# pcb_bare_tmc_2209.net
KiCad netlist of a schematic drawn in EAGLE
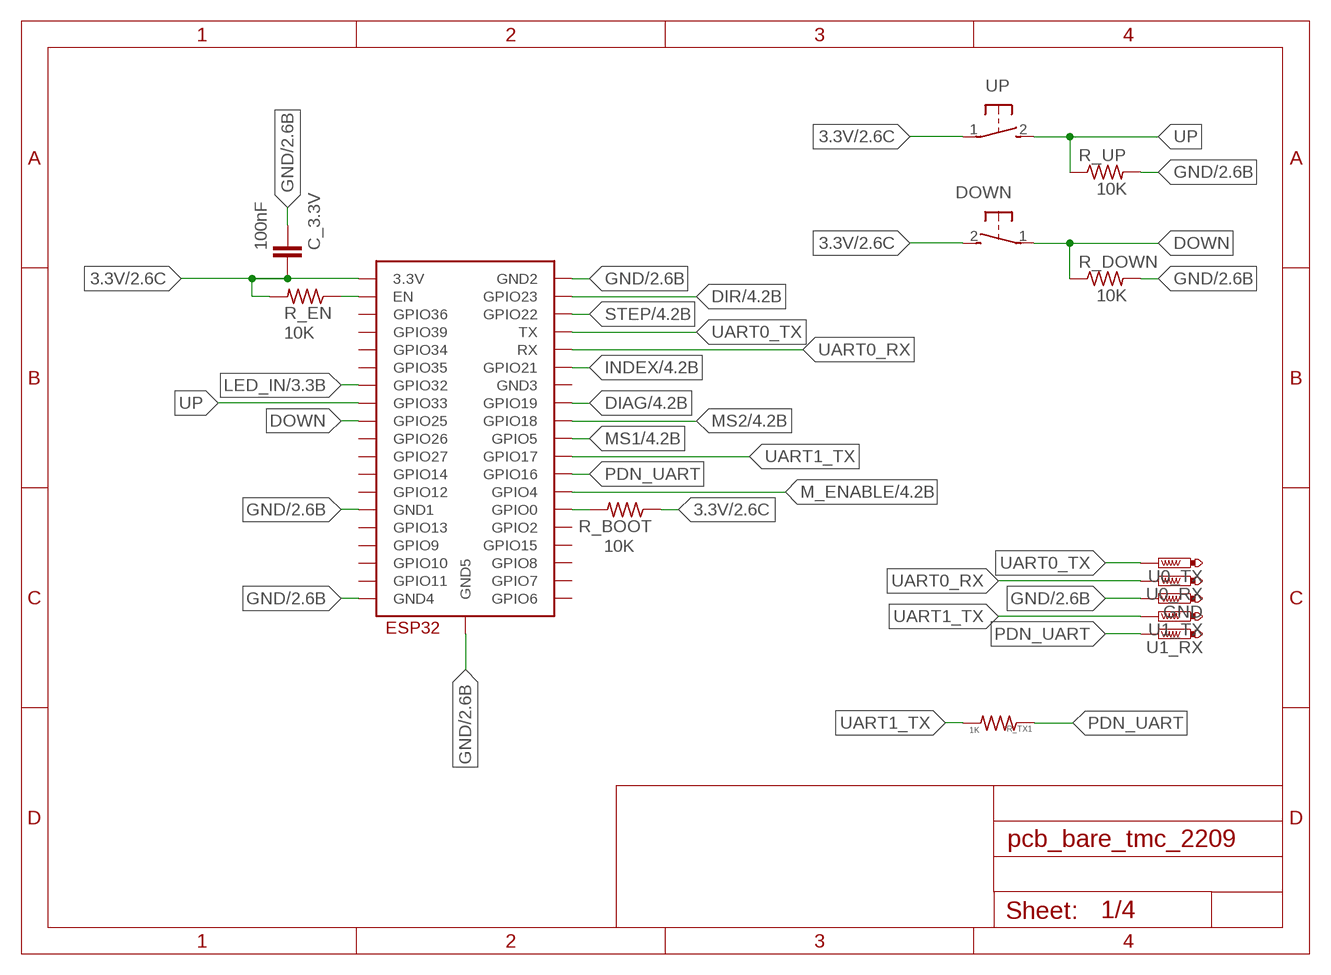
[diagram p0: schematic, sheet 1]
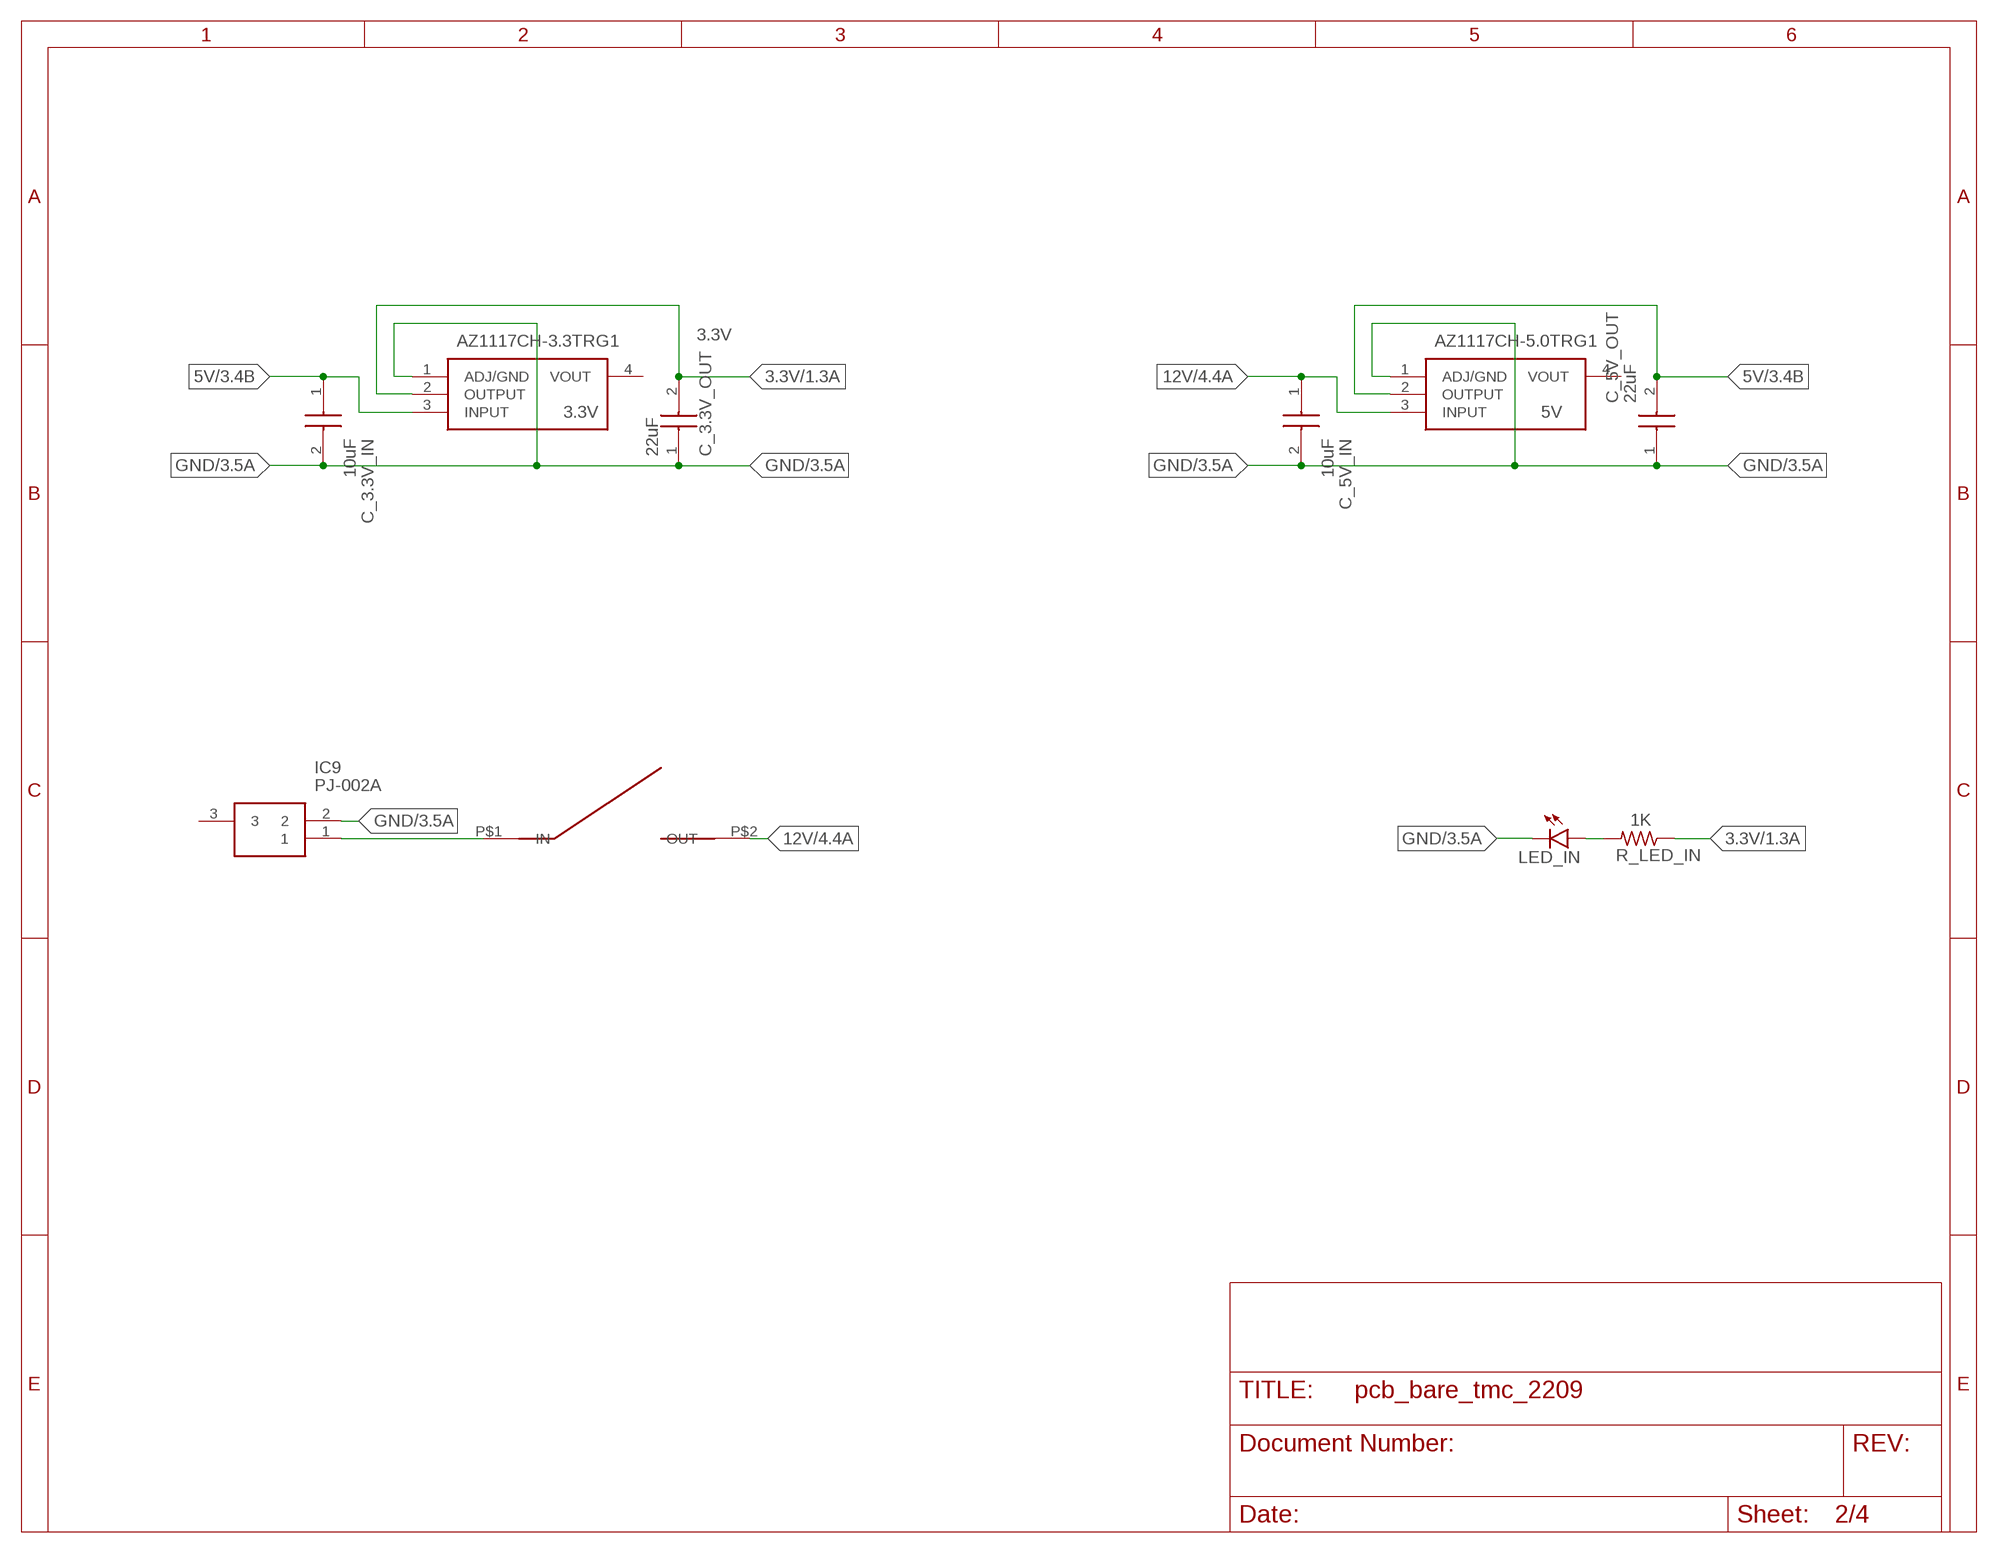
[diagram p1: schematic, sheet 2]
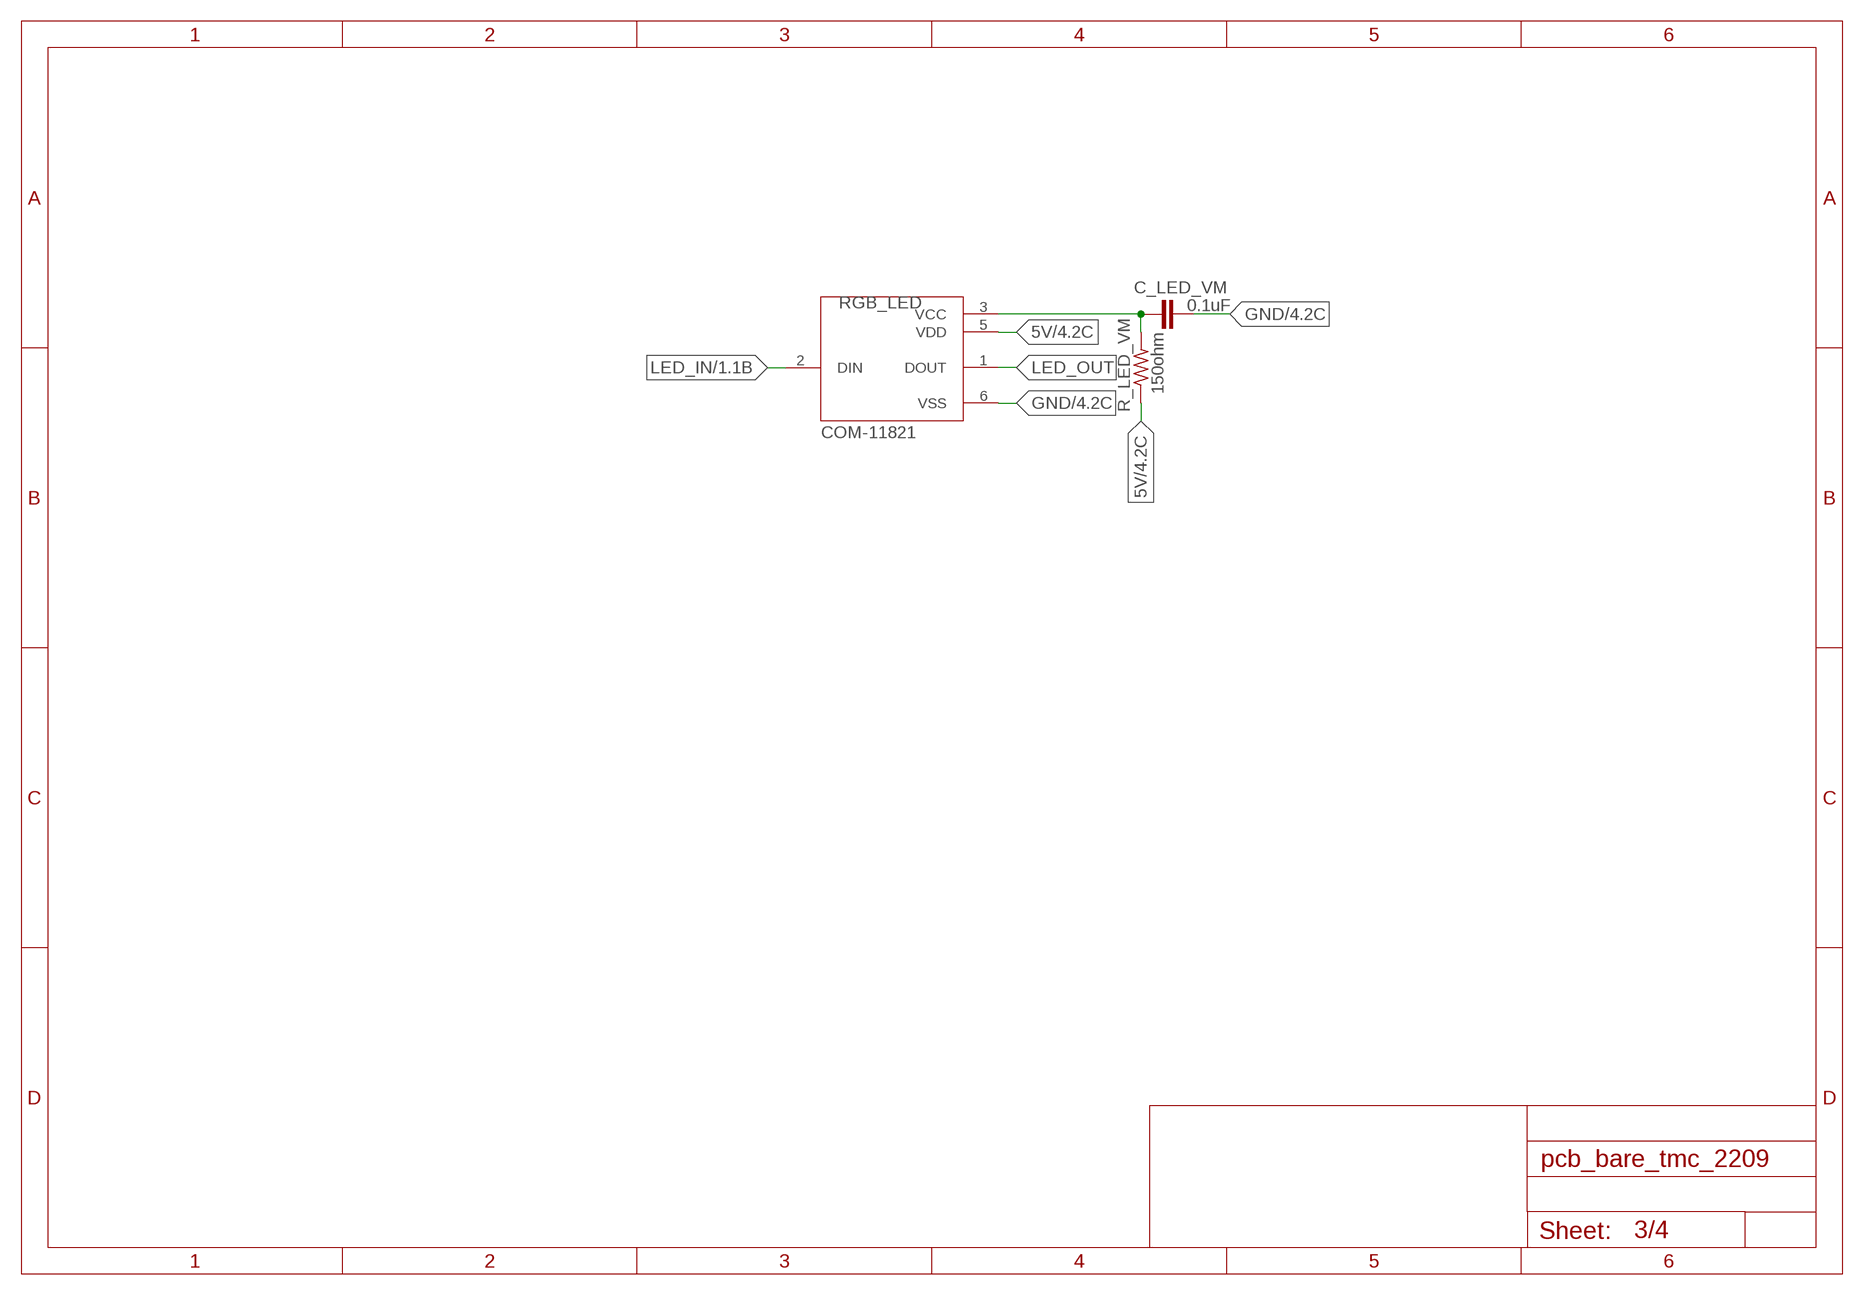
[diagram p2: schematic, sheet 3]
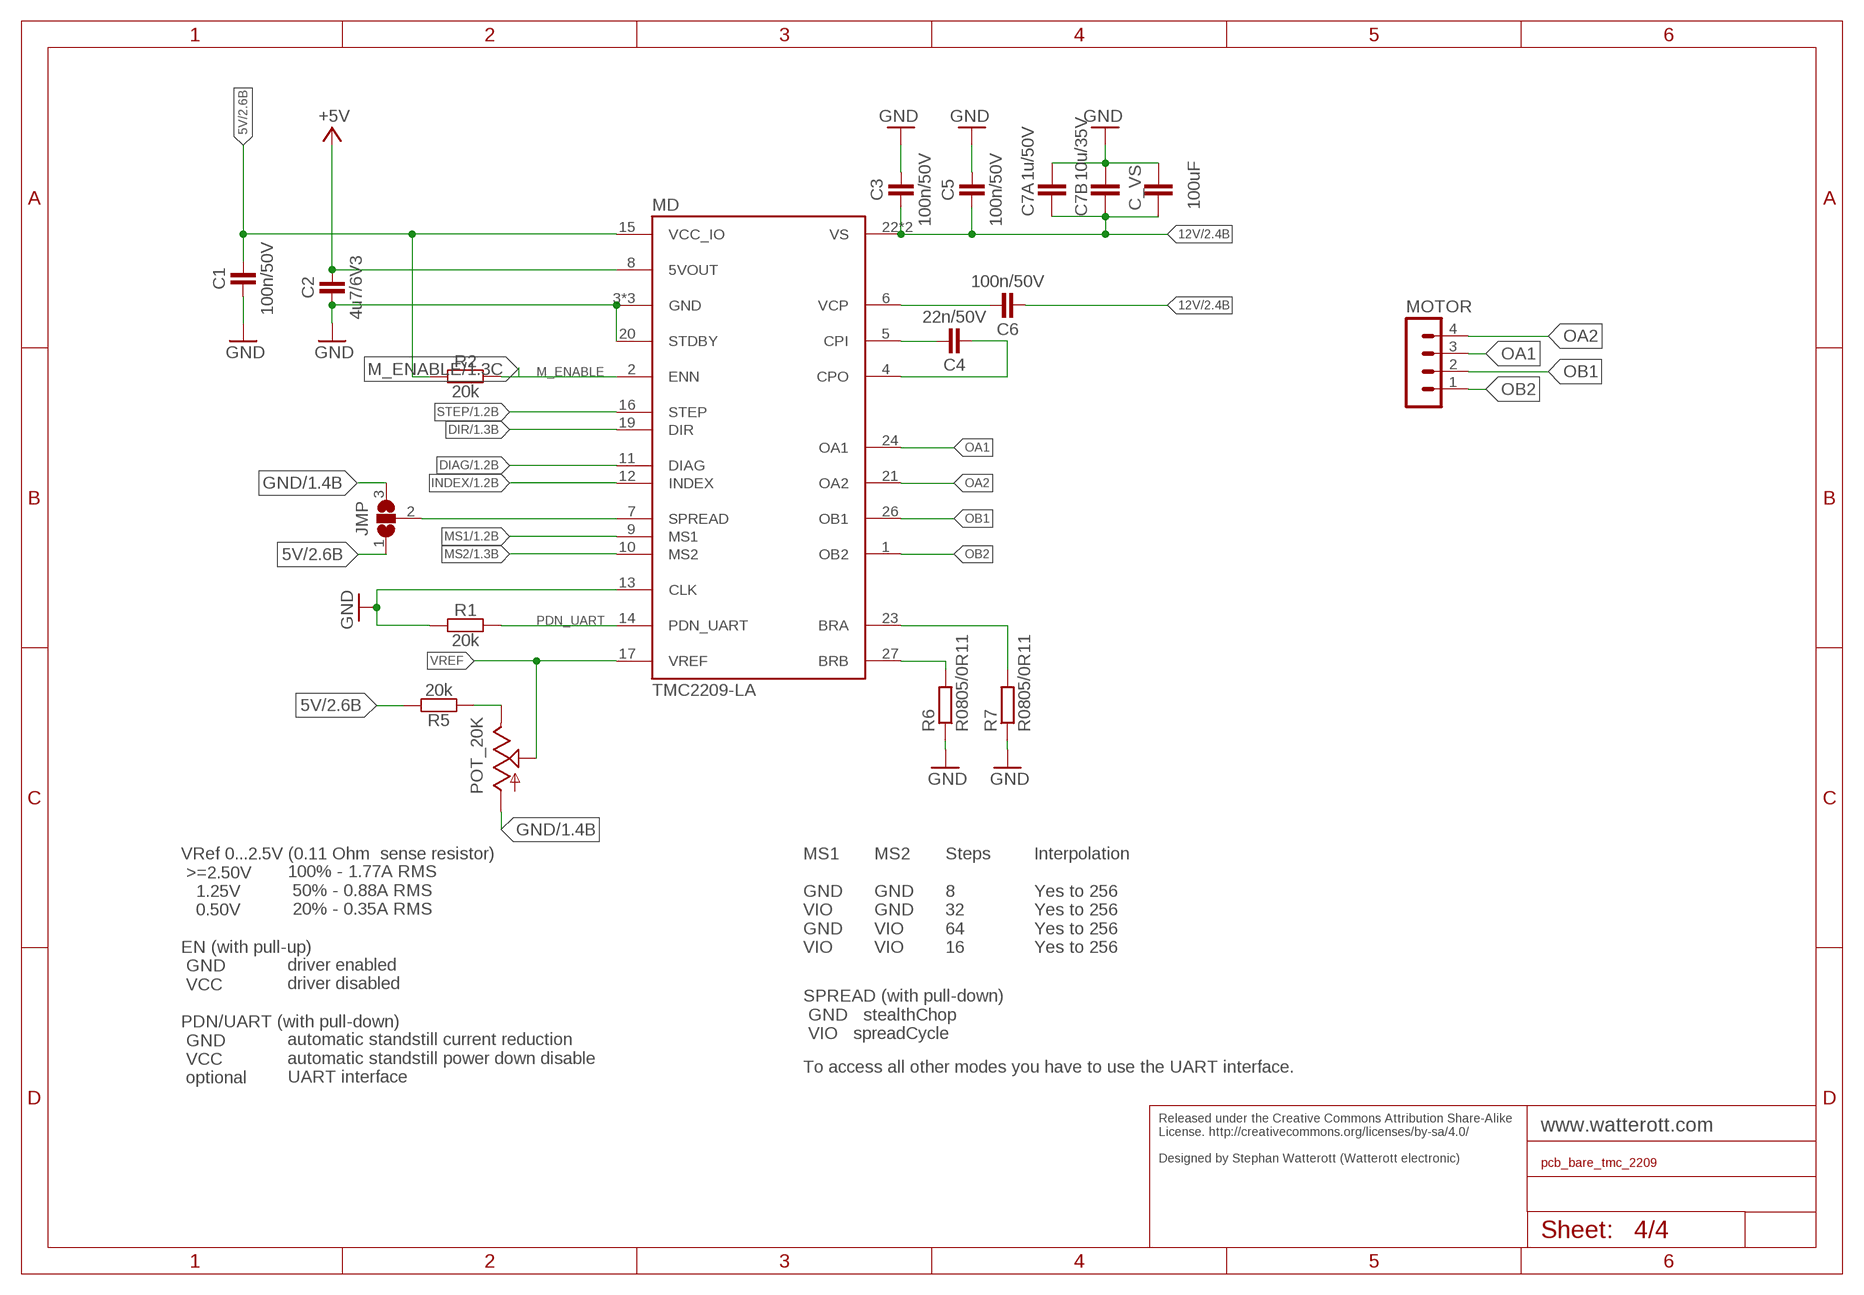
[diagram p3: schematic, sheet 4]

(export (version "E")
  (design (tool "Eeschema 10.0.6"))
  (components
    (comp (ref "C_LED_VM")
      (value "0.1uF")
      (footprint "eagle-import:C0805K")
      (libsource (lib "eagle-import") (part "rcl_334_C-EUC0805K"))
    )
    (comp (ref "RGB_LED")
      (value "COM-11821")
      (footprint "eagle-import:LED_COM-11821")
      (fields (field (name "MF") "SparkFun Electronics"))
      (libsource (lib "eagle-import") (part "COM-11821"))
    )
    (comp (ref "R_LED_VM")
      (value "150ohm")
      (footprint "eagle-import:R0805")
      (libsource (lib "eagle-import") (part "R-US_R0805"))
    )
    (comp (ref "C_3.3V")
      (value "100nF")
      (footprint "eagle-import:C0805K")
      (libsource (lib "eagle-import") (part "rcl_334_C-EUC0805K"))
    )
    (comp (ref "DOWN")
      (value "31-XX")
      (footprint "eagle-import:B3F-31XX")
      (fields (field (name "MPN") "B3F-3100"))
      (libsource (lib "eagle-import") (part "31-XX"))
    )
    (comp (ref "GND")
      (value "PTR1TP20SQ")
      (footprint "eagle-import:TP20SQ")
      (libsource (lib "eagle-import") (part "PTR1TP20SQ"))
    )
    (comp (ref "R_BOOT")
      (value "10K")
      (footprint "eagle-import:R0805")
      (libsource (lib "eagle-import") (part "R-US_R0805"))
    )
    (comp (ref "R_DOWN")
      (value "10K")
      (footprint "eagle-import:R0805")
      (libsource (lib "eagle-import") (part "R-US_R0805"))
    )
    (comp (ref "R_EN")
      (value "10K")
      (footprint "eagle-import:R0805")
      (libsource (lib "eagle-import") (part "R-US_R0805"))
    )
    (comp (ref "R_TX1")
      (value "1K")
      (footprint "eagle-import:R0805")
      (libsource (lib "eagle-import") (part "R-US_R0805"))
    )
    (comp (ref "R_UP")
      (value "10K")
      (footprint "eagle-import:R0805")
      (libsource (lib "eagle-import") (part "R-US_R0805"))
    )
    (comp (ref "U$2")
      (value "ESP32-WROOM")
      (footprint "eagle-import:ESP32-WROOM")
      (libsource (lib "eagle-import") (part "ESP32-WROOM"))
    )
    (comp (ref "U0_RX")
      (value "PTR1TP20SQ")
      (footprint "eagle-import:TP20SQ")
      (libsource (lib "eagle-import") (part "PTR1TP20SQ"))
    )
    (comp (ref "U0_TX")
      (value "PTR1TP20SQ")
      (footprint "eagle-import:TP20SQ")
      (libsource (lib "eagle-import") (part "PTR1TP20SQ"))
    )
    (comp (ref "U1_RX")
      (value "PTR1TP20SQ")
      (footprint "eagle-import:TP20SQ")
      (libsource (lib "eagle-import") (part "PTR1TP20SQ"))
    )
    (comp (ref "U1_TX")
      (value "PTR1TP20SQ")
      (footprint "eagle-import:TP20SQ")
      (libsource (lib "eagle-import") (part "PTR1TP20SQ"))
    )
    (comp (ref "UP")
      (value "31-XX")
      (footprint "eagle-import:B3F-31XX")
      (fields (field (name "MPN") "B3F-3100"))
      (libsource (lib "eagle-import") (part "31-XX"))
    )
    (comp (ref "3.3V")
      (value "AZ1117CH-3.3TRG1")
      (footprint "eagle-import:SOT230P700X180-4N")
      (fields (field (name "MOUSER_PART_NUMBER") "621-AZ1117CH-3.3TRG1"))
      (libsource (lib "eagle-import") (part "AZ1117CH-3.3TRG1"))
    )
    (comp (ref "5V")
      (value "AZ1117CH-5.0TRG1")
      (footprint "eagle-import:SOT230P700X180-4N")
      (fields (field (name "MOUSER_PART_NUMBER") "621-AZ1117CH-5.0TRG1"))
      (libsource (lib "eagle-import") (part "AZ1117CH-5.0TRG1"))
    )
    (comp (ref "C_3.3V_IN")
      (value "10uF")
      (footprint "eagle-import:CAPC2013X95N")
      (fields
        (field (name "MANUFACTURER_PART_NUMBER") "EMK212ABJ106KD-T")
        (field (name "MOUSER_PART_NUMBER") "963-EMK212ABJ106KD-T")
      )
      (libsource (lib "eagle-import") (part "EMK212ABJ106KD-T"))
    )
    (comp (ref "C_3.3V_OUT")
      (value "22uF")
      (footprint "eagle-import:CAPC3216X100N")
      (fields
        (field (name "MANUFACTURER_PART_NUMBER") "CL31A226MOCLNNC")
        (field (name "MOUSER_PART_NUMBER") "187-CL31A226MOCLNNC")
      )
      (libsource (lib "eagle-import") (part "CL31A226MOCLNNC"))
    )
    (comp (ref "C_5V_IN")
      (value "10uF")
      (footprint "eagle-import:CAPC2013X95N")
      (fields
        (field (name "MANUFACTURER_PART_NUMBER") "EMK212ABJ106KD-T")
        (field (name "MOUSER_PART_NUMBER") "963-EMK212ABJ106KD-T")
      )
      (libsource (lib "eagle-import") (part "EMK212ABJ106KD-T"))
    )
    (comp (ref "C_5V_OUT")
      (value "22uF")
      (footprint "eagle-import:CAPC3216X100N")
      (fields
        (field (name "MANUFACTURER_PART_NUMBER") "CL31A226MOCLNNC")
        (field (name "MOUSER_PART_NUMBER") "187-CL31A226MOCLNNC")
      )
      (libsource (lib "eagle-import") (part "CL31A226MOCLNNC"))
    )
    (comp (ref "IC9")
      (value "PJ-002A")
      (footprint "eagle-import:PJ002A")
      (fields (field (name "MOUSER_PART_NUMBER") "490-PJ-002A"))
      (libsource (lib "eagle-import") (part "PJ-002A"))
    )
    (comp (ref "LED_IN")
      (value "LEDSML0805")
      (footprint "eagle-import:SML0805")
      (libsource (lib "eagle-import") (part "LEDSML0805"))
    )
    (comp (ref "R_LED_IN")
      (value "1K")
      (footprint "eagle-import:R0805")
      (libsource (lib "eagle-import") (part "R-US_R0805"))
    )
    (comp (ref "U$1")
      (value "SPSTROCKERSWITCH2PIN")
      (footprint "eagle-import:SPST2PINROCKER")
      (libsource (lib "eagle-import") (part "SPSTROCKERSWITCH2PIN"))
    )
    (comp (ref "C1")
      (value "100n/50V")
      (footprint "eagle-import:C0402")
      (libsource (lib "eagle-import") (part "CAPACITOR-0402"))
    )
    (comp (ref "C2")
      (value "4u7/6V3")
      (footprint "eagle-import:C0402")
      (libsource (lib "eagle-import") (part "CAPACITOR-0402"))
    )
    (comp (ref "C3")
      (value "100n/50V")
      (footprint "eagle-import:C0402")
      (libsource (lib "eagle-import") (part "CAPACITOR-0402"))
    )
    (comp (ref "C4")
      (value "22n/50V")
      (footprint "eagle-import:C0402")
      (libsource (lib "eagle-import") (part "CAPACITOR-0402"))
    )
    (comp (ref "C5")
      (value "100n/50V")
      (footprint "eagle-import:C0402")
      (libsource (lib "eagle-import") (part "CAPACITOR-0402"))
    )
    (comp (ref "C6")
      (value "100n/50V")
      (footprint "eagle-import:C0402")
      (libsource (lib "eagle-import") (part "CAPACITOR-0402"))
    )
    (comp (ref "C7A")
      (value "1u/50V")
      (footprint "eagle-import:C0805")
      (libsource (lib "eagle-import") (part "C-EUC0805"))
    )
    (comp (ref "C7B")
      (value "10u/35V")
      (footprint "eagle-import:C1206")
      (libsource (lib "eagle-import") (part "C-EUC1206"))
    )
    (comp (ref "C_VS")
      (value "100uF")
      (footprint "eagle-import:C2.5-3")
      (libsource (lib "eagle-import") (part "C2,5-3"))
    )
    (comp (ref "JMP")
      (value "JUMPER3-0402-NC")
      (footprint "eagle-import:JUMPER3-0402_NC")
      (libsource (lib "eagle-import") (part "JUMPER3-0402-NC"))
    )
    (comp (ref "MD")
      (value "TMC2209-LA")
      (footprint "eagle-import:QFN28-PAD3.7")
      (libsource (lib "eagle-import") (part "TMC2209-LA"))
    )
    (comp (ref "MOTOR")
      (value "MA04-1")
      (footprint "eagle-import:MA04-1")
      (libsource (lib "eagle-import") (part "MA04-1"))
    )
    (comp (ref "POT_20K")
      (value "TRIM_US-3223G")
      (footprint "eagle-import:3223G")
      (libsource (lib "eagle-import") (part "TRIM_US-3223G"))
    )
    (comp (ref "R1")
      (value "20k")
      (footprint "eagle-import:C0402")
      (libsource (lib "eagle-import") (part "RESISTOR-0402"))
    )
    (comp (ref "R2")
      (value "20k")
      (footprint "eagle-import:C0402")
      (libsource (lib "eagle-import") (part "RESISTOR-0402"))
    )
    (comp (ref "R5")
      (value "20k")
      (footprint "eagle-import:C0402")
      (libsource (lib "eagle-import") (part "RESISTOR-0402"))
    )
    (comp (ref "R6")
      (value "R0805/0R11")
      (footprint "eagle-import:M0805")
      (libsource (lib "eagle-import") (part "R-EU_M0805"))
    )
    (comp (ref "R7")
      (value "R0805/0R11")
      (footprint "eagle-import:M0805")
      (libsource (lib "eagle-import") (part "R-EU_M0805"))
    )
  )
  (nets
    (net (code "1") (name "+5V") (class "Default")
      (node (ref "C2") (pin "2") (pinfunction "2_2") (pintype "passive"))
      (node (ref "MD") (pin "8") (pinfunction "5VOUT_8") (pintype "power_in"))
    )
    (net (code "2") (name "3.3V") (class "Default")
      (node (ref "3.3V") (pin "2") (pinfunction "OUTPUT_2") (pintype "bidirectional"))
      (node (ref "C_3.3V") (pin "2") (pinfunction "2_2") (pintype "passive"))
      (node (ref "C_3.3V_OUT") (pin "2") (pinfunction "2_2") (pintype "bidirectional"))
      (node (ref "DOWN") (pin "2") (pinfunction "S_2") (pintype "passive"))
      (node (ref "R_BOOT") (pin "1") (pinfunction "1_1") (pintype "passive"))
      (node (ref "R_EN") (pin "2") (pinfunction "2_2") (pintype "passive"))
      (node (ref "R_LED_IN") (pin "1") (pinfunction "1_1") (pintype "passive"))
      (node (ref "U$2") (pin "3V3") (pinfunction "3.3V_3V3") (pintype "bidirectional"))
      (node (ref "UP") (pin "1") (pinfunction "P_1") (pintype "passive"))
    )
    (net (code "3") (name "5V") (class "Default")
      (node (ref "3.3V") (pin "3") (pinfunction "INPUT_3") (pintype "bidirectional"))
      (node (ref "5V") (pin "2") (pinfunction "OUTPUT_2") (pintype "bidirectional"))
      (node (ref "C1") (pin "2") (pinfunction "2_2") (pintype "passive"))
      (node (ref "C_3.3V_IN") (pin "1") (pinfunction "1_1") (pintype "bidirectional"))
      (node (ref "C_5V_OUT") (pin "2") (pinfunction "2_2") (pintype "bidirectional"))
      (node (ref "JMP") (pin "1") (pinfunction "1_1") (pintype "passive"))
      (node (ref "MD") (pin "15") (pinfunction "VCC_IO_15") (pintype "power_in"))
      (node (ref "R2") (pin "1") (pinfunction "1_1") (pintype "passive"))
      (node (ref "R5") (pin "2") (pinfunction "2_2") (pintype "passive"))
      (node (ref "RGB_LED") (pin "5") (pinfunction "VDD_5") (pintype "power_in"))
      (node (ref "R_LED_VM") (pin "1") (pinfunction "1_1") (pintype "passive"))
    )
    (net (code "4") (name "12V") (class "Default")
      (node (ref "5V") (pin "3") (pinfunction "INPUT_3") (pintype "bidirectional"))
      (node (ref "C3") (pin "1") (pinfunction "1_1") (pintype "passive"))
      (node (ref "C5") (pin "1") (pinfunction "1_1") (pintype "passive"))
      (node (ref "C6") (pin "1") (pinfunction "1_1") (pintype "passive"))
      (node (ref "C7A") (pin "1") (pinfunction "1_1") (pintype "passive"))
      (node (ref "C7B") (pin "1") (pinfunction "1_1") (pintype "passive"))
      (node (ref "C_5V_IN") (pin "1") (pinfunction "1_1") (pintype "bidirectional"))
      (node (ref "C_VS") (pin "1") (pinfunction "1_1") (pintype "passive"))
      (node (ref "MD") (pin "22") (pinfunction "VS_22") (pintype "power_in"))
      (node (ref "MD") (pin "28") (pinfunction "VS_28") (pintype "power_in"))
      (node (ref "U$1") (pin "P$2") (pinfunction "OUT_P$2") (pintype "bidirectional"))
    )
    (net (code "5") (name "DIAG") (class "Default")
      (node (ref "MD") (pin "11") (pinfunction "DIAG_11") (pintype "bidirectional"))
      (node (ref "U$2") (pin "IO19") (pinfunction "GPIO19_IO19") (pintype "bidirectional"))
    )
    (net (code "6") (name "DIR") (class "Default")
      (node (ref "MD") (pin "19") (pinfunction "DIR_19") (pintype "bidirectional"))
      (node (ref "U$2") (pin "IO23") (pinfunction "GPIO23_IO23") (pintype "bidirectional"))
    )
    (net (code "7") (name "DOWN") (class "Default")
      (node (ref "DOWN") (pin "1") (pinfunction "P_1") (pintype "passive"))
      (node (ref "R_DOWN") (pin "1") (pinfunction "1_1") (pintype "passive"))
      (node (ref "U$2") (pin "IO25") (pinfunction "GPIO25_IO25") (pintype "bidirectional"))
    )
    (net (code "8") (name "GND") (class "Default")
      (node (ref "3.3V") (pin "1") (pinfunction "ADJ/GND_1") (pintype "bidirectional"))
      (node (ref "5V") (pin "1") (pinfunction "ADJ/GND_1") (pintype "bidirectional"))
      (node (ref "C1") (pin "1") (pinfunction "1_1") (pintype "passive"))
      (node (ref "C2") (pin "1") (pinfunction "1_1") (pintype "passive"))
      (node (ref "C3") (pin "2") (pinfunction "2_2") (pintype "passive"))
      (node (ref "C5") (pin "2") (pinfunction "2_2") (pintype "passive"))
      (node (ref "C7A") (pin "2") (pinfunction "2_2") (pintype "passive"))
      (node (ref "C7B") (pin "2") (pinfunction "2_2") (pintype "passive"))
      (node (ref "C_3.3V") (pin "1") (pinfunction "1_1") (pintype "passive"))
      (node (ref "C_3.3V_IN") (pin "2") (pinfunction "2_2") (pintype "bidirectional"))
      (node (ref "C_3.3V_OUT") (pin "1") (pinfunction "1_1") (pintype "bidirectional"))
      (node (ref "C_5V_IN") (pin "2") (pinfunction "2_2") (pintype "bidirectional"))
      (node (ref "C_5V_OUT") (pin "1") (pinfunction "1_1") (pintype "bidirectional"))
      (node (ref "C_LED_VM") (pin "2") (pinfunction "2_2") (pintype "passive"))
      (node (ref "C_VS") (pin "2") (pinfunction "2_2") (pintype "passive"))
      (node (ref "GND") (pin "TP") (pinfunction "TP_TP") (pintype "input"))
      (node (ref "IC9") (pin "2") (pinfunction "2_2") (pintype "bidirectional"))
      (node (ref "JMP") (pin "3") (pinfunction "3_3") (pintype "passive"))
      (node (ref "LED_IN") (pin "C") (pinfunction "C_C") (pintype "passive"))
      (node (ref "MD") (pin "13") (pinfunction "CLK_13") (pintype "bidirectional"))
      (node (ref "MD") (pin "18") (pinfunction "GND_18") (pintype "power_in"))
      (node (ref "MD") (pin "20") (pinfunction "STDBY_20") (pintype "bidirectional"))
      (node (ref "MD") (pin "3") (pinfunction "GND_3") (pintype "power_in"))
      (node (ref "MD") (pin "TP") (pinfunction "GND_TP") (pintype "power_in"))
      (node (ref "POT_20K") (pin "1") (pinfunction "A_1") (pintype "passive"))
      (node (ref "R1") (pin "1") (pinfunction "1_1") (pintype "passive"))
      (node (ref "R6") (pin "1") (pinfunction "1_1") (pintype "passive"))
      (node (ref "R7") (pin "1") (pinfunction "1_1") (pintype "passive"))
      (node (ref "RGB_LED") (pin "6") (pinfunction "VSS_6") (pintype "power_in"))
      (node (ref "R_DOWN") (pin "2") (pinfunction "2_2") (pintype "passive"))
      (node (ref "R_UP") (pin "2") (pinfunction "2_2") (pintype "passive"))
      (node (ref "U$2") (pin "GND1") (pinfunction "GND1_GND1") (pintype "bidirectional"))
      (node (ref "U$2") (pin "GND2") (pinfunction "GND2_GND2") (pintype "bidirectional"))
      (node (ref "U$2") (pin "GND4") (pinfunction "GND4_GND4") (pintype "bidirectional"))
      (node (ref "U$2") (pin "GND5") (pinfunction "GND5_GND5") (pintype "bidirectional"))
    )
    (net (code "9") (name "INDEX") (class "Default")
      (node (ref "MD") (pin "12") (pinfunction "INDEX_12") (pintype "bidirectional"))
      (node (ref "U$2") (pin "IO21") (pinfunction "GPIO21_IO21") (pintype "bidirectional"))
    )
    (net (code "10") (name "LED_IN") (class "Default")
      (node (ref "RGB_LED") (pin "2") (pinfunction "DIN_2") (pintype "input"))
      (node (ref "U$2") (pin "IO32") (pinfunction "GPIO32_IO32") (pintype "bidirectional"))
    )
    (net (code "11") (name "LED_OUT") (class "Default")
      (node (ref "RGB_LED") (pin "1") (pinfunction "DOUT_1") (pintype "output"))
    )
    (net (code "12") (name "MS1") (class "Default")
      (node (ref "MD") (pin "9") (pinfunction "MS1_9") (pintype "bidirectional"))
      (node (ref "U$2") (pin "IO5") (pinfunction "GPIO5_IO5") (pintype "bidirectional"))
    )
    (net (code "13") (name "MS2") (class "Default")
      (node (ref "MD") (pin "10") (pinfunction "MS2_10") (pintype "bidirectional"))
      (node (ref "U$2") (pin "IO18") (pinfunction "GPIO18_IO18") (pintype "bidirectional"))
    )
    (net (code "14") (name "M_ENABLE") (class "Default")
      (node (ref "MD") (pin "2") (pinfunction "ENN_2") (pintype "bidirectional"))
      (node (ref "R2") (pin "2") (pinfunction "2_2") (pintype "passive"))
      (node (ref "U$2") (pin "IO4") (pinfunction "GPIO4_IO4") (pintype "bidirectional"))
    )
    (net (code "15") (name "Net-(LED_IN-PadA)") (class "Default")
      (node (ref "LED_IN") (pin "A") (pinfunction "A_A") (pintype "passive"))
      (node (ref "R_LED_IN") (pin "2") (pinfunction "2_2") (pintype "passive"))
    )
    (net (code "16") (name "Net-(MD-BRA)") (class "Default")
      (node (ref "MD") (pin "23") (pinfunction "BRA_23") (pintype "output"))
      (node (ref "R7") (pin "2") (pinfunction "2_2") (pintype "passive"))
    )
    (net (code "17") (name "Net-(MD-BRB)") (class "Default")
      (node (ref "MD") (pin "27") (pinfunction "BRB_27") (pintype "output"))
      (node (ref "R6") (pin "2") (pinfunction "2_2") (pintype "passive"))
    )
    (net (code "18") (name "Net-(MD-CPI)") (class "Default")
      (node (ref "C4") (pin "2") (pinfunction "2_2") (pintype "passive"))
      (node (ref "MD") (pin "5") (pinfunction "CPI_5") (pintype "passive"))
    )
    (net (code "19") (name "Net-(MD-CPO)") (class "Default")
      (node (ref "C4") (pin "1") (pinfunction "1_1") (pintype "passive"))
      (node (ref "MD") (pin "4") (pinfunction "CPO_4") (pintype "passive"))
    )
    (net (code "20") (name "Net-(MD-SPREAD)") (class "Default")
      (node (ref "JMP") (pin "2") (pinfunction "2_2") (pintype "passive"))
      (node (ref "MD") (pin "7") (pinfunction "SPREAD_7") (pintype "bidirectional"))
    )
    (net (code "21") (name "Net-(MD-VCP)") (class "Default")
      (node (ref "C6") (pin "2") (pinfunction "2_2") (pintype "passive"))
      (node (ref "MD") (pin "6") (pinfunction "VCP_6") (pintype "passive"))
    )
    (net (code "22") (name "Net-(POT_20K-E)") (class "Default")
      (node (ref "POT_20K") (pin "3") (pinfunction "E_3") (pintype "passive"))
      (node (ref "R5") (pin "1") (pinfunction "1_1") (pintype "passive"))
    )
    (net (code "23") (name "Net-(RGB_LED-VCC)") (class "Default")
      (node (ref "C_LED_VM") (pin "1") (pinfunction "1_1") (pintype "passive"))
      (node (ref "RGB_LED") (pin "3") (pinfunction "VCC_3") (pintype "power_in"))
      (node (ref "R_LED_VM") (pin "2") (pinfunction "2_2") (pintype "passive"))
    )
    (net (code "24") (name "Net-(R_EN-Pad1)") (class "Default")
      (node (ref "R_EN") (pin "1") (pinfunction "1_1") (pintype "passive"))
      (node (ref "U$2") (pin "EN") (pinfunction "EN_EN") (pintype "bidirectional"))
    )
    (net (code "25") (name "Net-(U$1-IN)") (class "Default")
      (node (ref "IC9") (pin "1") (pinfunction "1_1") (pintype "bidirectional"))
      (node (ref "U$1") (pin "P$1") (pinfunction "IN_P$1") (pintype "bidirectional"))
    )
    (net (code "26") (name "Net-(U$2-GPIO0)") (class "Default")
      (node (ref "R_BOOT") (pin "2") (pinfunction "2_2") (pintype "passive"))
      (node (ref "U$2") (pin "IO0") (pinfunction "GPIO0_IO0") (pintype "bidirectional"))
    )
    (net (code "27") (name "OA1") (class "Default")
      (node (ref "MD") (pin "24") (pinfunction "OA1_24") (pintype "output"))
      (node (ref "MOTOR") (pin "3") (pinfunction "3_3") (pintype "passive"))
    )
    (net (code "28") (name "OA2") (class "Default")
      (node (ref "MD") (pin "21") (pinfunction "OA2_21") (pintype "output"))
      (node (ref "MOTOR") (pin "4") (pinfunction "4_4") (pintype "passive"))
    )
    (net (code "29") (name "OB1") (class "Default")
      (node (ref "MD") (pin "26") (pinfunction "OB1_26") (pintype "output"))
      (node (ref "MOTOR") (pin "2") (pinfunction "2_2") (pintype "passive"))
    )
    (net (code "30") (name "OB2") (class "Default")
      (node (ref "MD") (pin "1") (pinfunction "OB2_1") (pintype "output"))
      (node (ref "MOTOR") (pin "1") (pinfunction "1_1") (pintype "passive"))
    )
    (net (code "31") (name "PDN_UART") (class "Default")
      (node (ref "MD") (pin "14") (pinfunction "PDN_UART_14") (pintype "bidirectional"))
      (node (ref "R1") (pin "2") (pinfunction "2_2") (pintype "passive"))
      (node (ref "R_TX1") (pin "1") (pinfunction "1_1") (pintype "passive"))
      (node (ref "U$2") (pin "IO16") (pinfunction "GPIO16_IO16") (pintype "bidirectional"))
      (node (ref "U1_RX") (pin "TP") (pinfunction "TP_TP") (pintype "input"))
    )
    (net (code "32") (name "STEP") (class "Default")
      (node (ref "MD") (pin "16") (pinfunction "STEP_16") (pintype "bidirectional"))
      (node (ref "U$2") (pin "IO22") (pinfunction "GPIO22_IO22") (pintype "bidirectional"))
    )
    (net (code "33") (name "UART0_RX") (class "Default")
      (node (ref "U$2") (pin "RX") (pinfunction "RX_RX") (pintype "bidirectional"))
      (node (ref "U0_RX") (pin "TP") (pinfunction "TP_TP") (pintype "input"))
    )
    (net (code "34") (name "UART0_TX") (class "Default")
      (node (ref "U$2") (pin "TX") (pinfunction "TX_TX") (pintype "bidirectional"))
      (node (ref "U0_TX") (pin "TP") (pinfunction "TP_TP") (pintype "input"))
    )
    (net (code "35") (name "UART1_TX") (class "Default")
      (node (ref "R_TX1") (pin "2") (pinfunction "2_2") (pintype "passive"))
      (node (ref "U$2") (pin "IO17") (pinfunction "GPIO17_IO17") (pintype "bidirectional"))
      (node (ref "U1_TX") (pin "TP") (pinfunction "TP_TP") (pintype "input"))
    )
    (net (code "36") (name "UP") (class "Default")
      (node (ref "R_UP") (pin "1") (pinfunction "1_1") (pintype "passive"))
      (node (ref "U$2") (pin "IO33") (pinfunction "GPIO33_IO33") (pintype "bidirectional"))
      (node (ref "UP") (pin "2") (pinfunction "S_2") (pintype "passive"))
    )
    (net (code "37") (name "VREF") (class "Default")
      (node (ref "MD") (pin "17") (pinfunction "VREF_17") (pintype "passive"))
      (node (ref "POT_20K") (pin "2") (pinfunction "S_2") (pintype "passive"))
    )
    (net (code "38") (name "unconnected-(3.3V-VOUT-Pad4)") (class "Default")
      (node (ref "3.3V") (pin "4") (pinfunction "VOUT_4") (pintype "bidirectional"))
    )
    (net (code "39") (name "unconnected-(5V-VOUT-Pad4)") (class "Default")
      (node (ref "5V") (pin "4") (pinfunction "VOUT_4") (pintype "bidirectional"))
    )
    (net (code "40") (name "unconnected-(IC9-Pad3)") (class "Default")
      (node (ref "IC9") (pin "3") (pinfunction "3_3") (pintype "bidirectional"))
    )
    (net (code "41") (name "unconnected-(U$2-GPIO2-PadIO2)") (class "Default")
      (node (ref "U$2") (pin "IO2") (pinfunction "GPIO2_IO2") (pintype "bidirectional"))
    )
    (net (code "42") (name "unconnected-(U$2-GPIO6-PadCLK)") (class "Default")
      (node (ref "U$2") (pin "CLK") (pinfunction "GPIO6_CLK") (pintype "bidirectional"))
    )
    (net (code "43") (name "unconnected-(U$2-GPIO7-PadSD0)") (class "Default")
      (node (ref "U$2") (pin "SD0") (pinfunction "GPIO7_SD0") (pintype "bidirectional"))
    )
    (net (code "44") (name "unconnected-(U$2-GPIO8-PadSD1)") (class "Default")
      (node (ref "U$2") (pin "SD1") (pinfunction "GPIO8_SD1") (pintype "bidirectional"))
    )
    (net (code "45") (name "unconnected-(U$2-GPIO9-PadSD2)") (class "Default")
      (node (ref "U$2") (pin "SD2") (pinfunction "GPIO9_SD2") (pintype "bidirectional"))
    )
    (net (code "46") (name "unconnected-(U$2-GPIO10-PadSD3)") (class "Default")
      (node (ref "U$2") (pin "SD3") (pinfunction "GPIO10_SD3") (pintype "bidirectional"))
    )
    (net (code "47") (name "unconnected-(U$2-GPIO11-PadCMD)") (class "Default")
      (node (ref "U$2") (pin "CMD") (pinfunction "GPIO11_CMD") (pintype "bidirectional"))
    )
    (net (code "48") (name "unconnected-(U$2-GPIO12-PadIO12)") (class "Default")
      (node (ref "U$2") (pin "IO12") (pinfunction "GPIO12_IO12") (pintype "bidirectional"))
    )
    (net (code "49") (name "unconnected-(U$2-GPIO13-PadIO13)") (class "Default")
      (node (ref "U$2") (pin "IO13") (pinfunction "GPIO13_IO13") (pintype "bidirectional"))
    )
    (net (code "50") (name "unconnected-(U$2-GPIO14-PadIO14)") (class "Default")
      (node (ref "U$2") (pin "IO14") (pinfunction "GPIO14_IO14") (pintype "bidirectional"))
    )
    (net (code "51") (name "unconnected-(U$2-GPIO15-PadIO15)") (class "Default")
      (node (ref "U$2") (pin "IO15") (pinfunction "GPIO15_IO15") (pintype "bidirectional"))
    )
    (net (code "52") (name "unconnected-(U$2-GPIO26-PadIO26)") (class "Default")
      (node (ref "U$2") (pin "IO26") (pinfunction "GPIO26_IO26") (pintype "bidirectional"))
    )
    (net (code "53") (name "unconnected-(U$2-GPIO27-PadIO27)") (class "Default")
      (node (ref "U$2") (pin "IO27") (pinfunction "GPIO27_IO27") (pintype "bidirectional"))
    )
    (net (code "54") (name "unconnected-(U$2-GPIO34-PadIO34)") (class "Default")
      (node (ref "U$2") (pin "IO34") (pinfunction "GPIO34_IO34") (pintype "bidirectional"))
    )
    (net (code "55") (name "unconnected-(U$2-GPIO35-PadIO35)") (class "Default")
      (node (ref "U$2") (pin "IO35") (pinfunction "GPIO35_IO35") (pintype "bidirectional"))
    )
    (net (code "56") (name "unconnected-(U$2-GPIO36-PadSENSOR_VP)") (class "Default")
      (node (ref "U$2") (pin "SENSOR_VP") (pinfunction "GPIO36_SENSOR_VP") (pintype "bidirectional"))
    )
    (net (code "57") (name "unconnected-(U$2-GPIO39-PadSENSOR_VN)") (class "Default")
      (node (ref "U$2") (pin "SENSOR_VN") (pinfunction "GPIO39_SENSOR_VN") (pintype "bidirectional"))
    )
    (net (code "58") (name "unconnected-(U$2-PadGND3)") (class "Default")
      (node (ref "U$2") (pin "GND3") (pinfunction "GND3_GND3") (pintype "bidirectional"))
    )
  )
)
